# qo-100-generic-filter.net
KiCad netlist of a schematic drawn in EAGLE
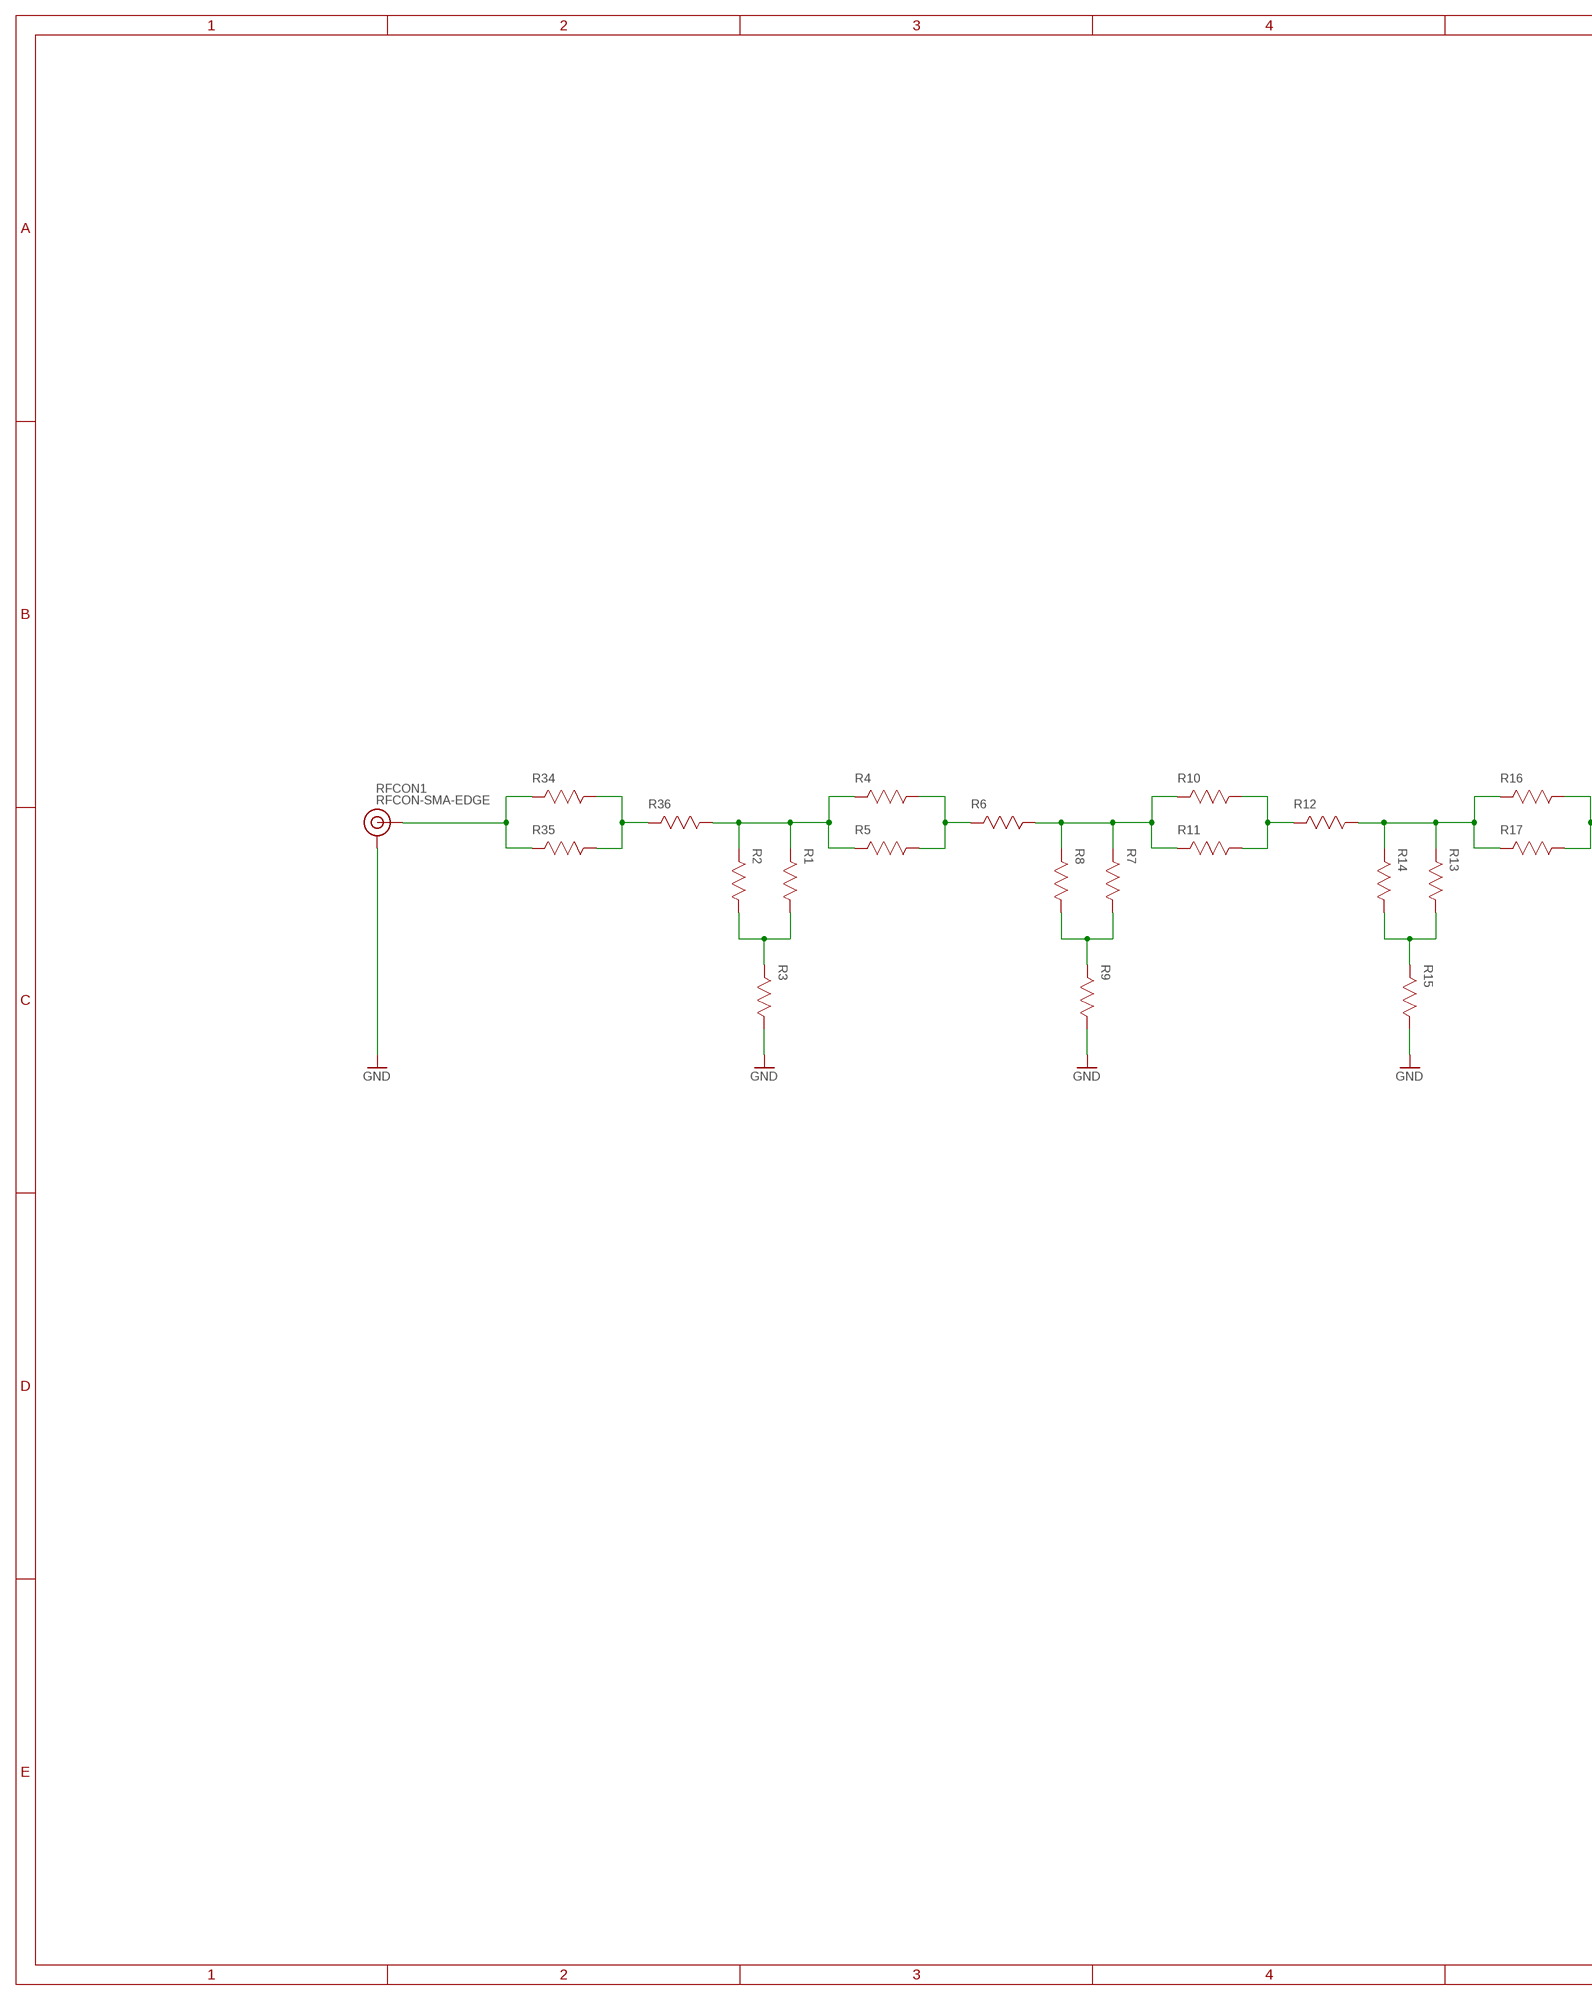
[diagram p0: schematic, sheet 1, part 1 of 2]
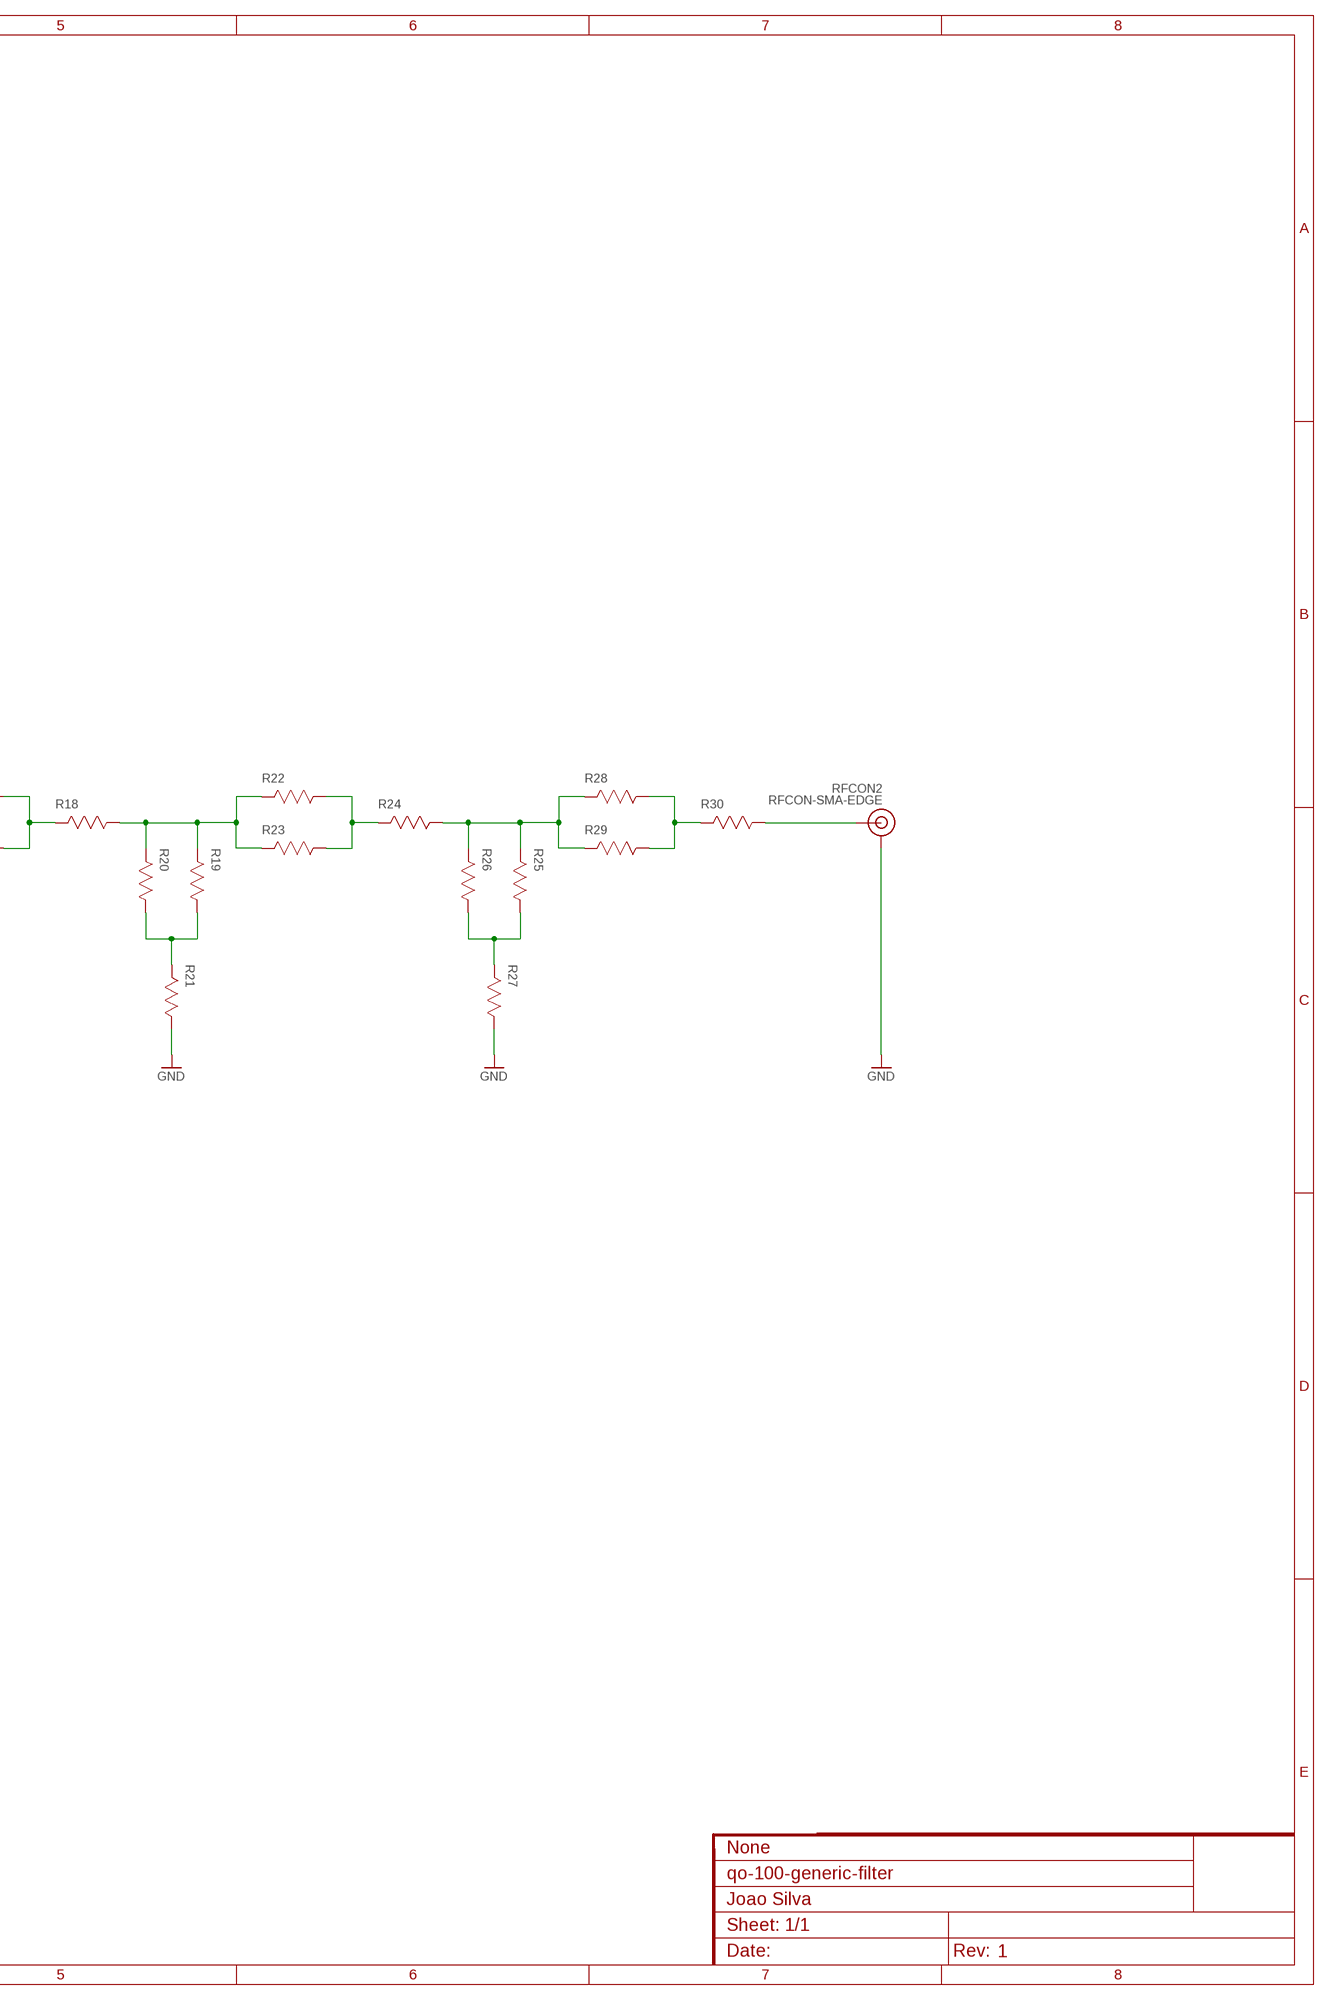
[diagram p1: schematic, sheet 1, part 2 of 2]

(export (version "E")
  (design (tool "Eeschema 10.0.6"))
  (components
    (comp (ref "R1")
      (value "RESISTOR-0603")
      (footprint "eagle-import:RES0603")
      (libsource (lib "eagle-import") (part "RESISTOR-0603"))
    )
    (comp (ref "R2")
      (value "RESISTOR-0603")
      (footprint "eagle-import:RES0603")
      (libsource (lib "eagle-import") (part "RESISTOR-0603"))
    )
    (comp (ref "R3")
      (value "RESISTOR-0603")
      (footprint "eagle-import:RES0603")
      (libsource (lib "eagle-import") (part "RESISTOR-0603"))
    )
    (comp (ref "R4")
      (value "RESISTOR-0603")
      (footprint "eagle-import:RES0603")
      (libsource (lib "eagle-import") (part "RESISTOR-0603"))
    )
    (comp (ref "R5")
      (value "RESISTOR-0603")
      (footprint "eagle-import:RES0603")
      (libsource (lib "eagle-import") (part "RESISTOR-0603"))
    )
    (comp (ref "R6")
      (value "RESISTOR-0603")
      (footprint "eagle-import:RES0603")
      (libsource (lib "eagle-import") (part "RESISTOR-0603"))
    )
    (comp (ref "R7")
      (value "RESISTOR-0603")
      (footprint "eagle-import:RES0603")
      (libsource (lib "eagle-import") (part "RESISTOR-0603"))
    )
    (comp (ref "R8")
      (value "RESISTOR-0603")
      (footprint "eagle-import:RES0603")
      (libsource (lib "eagle-import") (part "RESISTOR-0603"))
    )
    (comp (ref "R9")
      (value "RESISTOR-0603")
      (footprint "eagle-import:RES0603")
      (libsource (lib "eagle-import") (part "RESISTOR-0603"))
    )
    (comp (ref "R10")
      (value "RESISTOR-0603")
      (footprint "eagle-import:RES0603")
      (libsource (lib "eagle-import") (part "RESISTOR-0603"))
    )
    (comp (ref "R11")
      (value "RESISTOR-0603")
      (footprint "eagle-import:RES0603")
      (libsource (lib "eagle-import") (part "RESISTOR-0603"))
    )
    (comp (ref "R12")
      (value "RESISTOR-0603")
      (footprint "eagle-import:RES0603")
      (libsource (lib "eagle-import") (part "RESISTOR-0603"))
    )
    (comp (ref "R13")
      (value "RESISTOR-0603")
      (footprint "eagle-import:RES0603")
      (libsource (lib "eagle-import") (part "RESISTOR-0603"))
    )
    (comp (ref "R14")
      (value "RESISTOR-0603")
      (footprint "eagle-import:RES0603")
      (libsource (lib "eagle-import") (part "RESISTOR-0603"))
    )
    (comp (ref "R15")
      (value "RESISTOR-0603")
      (footprint "eagle-import:RES0603")
      (libsource (lib "eagle-import") (part "RESISTOR-0603"))
    )
    (comp (ref "R16")
      (value "RESISTOR-0603")
      (footprint "eagle-import:RES0603")
      (libsource (lib "eagle-import") (part "RESISTOR-0603"))
    )
    (comp (ref "R17")
      (value "RESISTOR-0603")
      (footprint "eagle-import:RES0603")
      (libsource (lib "eagle-import") (part "RESISTOR-0603"))
    )
    (comp (ref "R18")
      (value "RESISTOR-0603")
      (footprint "eagle-import:RES0603")
      (libsource (lib "eagle-import") (part "RESISTOR-0603"))
    )
    (comp (ref "R19")
      (value "RESISTOR-0603")
      (footprint "eagle-import:RES0603")
      (libsource (lib "eagle-import") (part "RESISTOR-0603"))
    )
    (comp (ref "R20")
      (value "RESISTOR-0603")
      (footprint "eagle-import:RES0603")
      (libsource (lib "eagle-import") (part "RESISTOR-0603"))
    )
    (comp (ref "R21")
      (value "RESISTOR-0603")
      (footprint "eagle-import:RES0603")
      (libsource (lib "eagle-import") (part "RESISTOR-0603"))
    )
    (comp (ref "R22")
      (value "RESISTOR-0603")
      (footprint "eagle-import:RES0603")
      (libsource (lib "eagle-import") (part "RESISTOR-0603"))
    )
    (comp (ref "R23")
      (value "RESISTOR-0603")
      (footprint "eagle-import:RES0603")
      (libsource (lib "eagle-import") (part "RESISTOR-0603"))
    )
    (comp (ref "R24")
      (value "RESISTOR-0603")
      (footprint "eagle-import:RES0603")
      (libsource (lib "eagle-import") (part "RESISTOR-0603"))
    )
    (comp (ref "R25")
      (value "RESISTOR-0603")
      (footprint "eagle-import:RES0603")
      (libsource (lib "eagle-import") (part "RESISTOR-0603"))
    )
    (comp (ref "R26")
      (value "RESISTOR-0603")
      (footprint "eagle-import:RES0603")
      (libsource (lib "eagle-import") (part "RESISTOR-0603"))
    )
    (comp (ref "R27")
      (value "RESISTOR-0603")
      (footprint "eagle-import:RES0603")
      (libsource (lib "eagle-import") (part "RESISTOR-0603"))
    )
    (comp (ref "R28")
      (value "RESISTOR-0603")
      (footprint "eagle-import:RES0603")
      (libsource (lib "eagle-import") (part "RESISTOR-0603"))
    )
    (comp (ref "R29")
      (value "RESISTOR-0603")
      (footprint "eagle-import:RES0603")
      (libsource (lib "eagle-import") (part "RESISTOR-0603"))
    )
    (comp (ref "R30")
      (value "RESISTOR-0603")
      (footprint "eagle-import:RES0603")
      (libsource (lib "eagle-import") (part "RESISTOR-0603"))
    )
    (comp (ref "R34")
      (value "RESISTOR-0603")
      (footprint "eagle-import:RES0603")
      (libsource (lib "eagle-import") (part "RESISTOR-0603"))
    )
    (comp (ref "R35")
      (value "RESISTOR-0603")
      (footprint "eagle-import:RES0603")
      (libsource (lib "eagle-import") (part "RESISTOR-0603"))
    )
    (comp (ref "R36")
      (value "RESISTOR-0603")
      (footprint "eagle-import:RES0603")
      (libsource (lib "eagle-import") (part "RESISTOR-0603"))
    )
    (comp (ref "RFCON1")
      (value "RFCON-SMA-EDGE")
      (footprint "eagle-import:SMA-EDGE")
      (libsource (lib "eagle-import") (part "RFCON-SMA-EDGE"))
    )
    (comp (ref "RFCON2")
      (value "RFCON-SMA-EDGE")
      (footprint "eagle-import:SMA-EDGE")
      (libsource (lib "eagle-import") (part "RFCON-SMA-EDGE"))
    )
  )
  (nets
    (net (code "1") (name "GND") (class "Default")
      (node (ref "R15") (pin "1") (pinfunction "1_1") (pintype "passive"))
      (node (ref "R21") (pin "1") (pinfunction "1_1") (pintype "passive"))
      (node (ref "R27") (pin "1") (pinfunction "1_1") (pintype "passive"))
      (node (ref "R3") (pin "1") (pinfunction "1_1") (pintype "passive"))
      (node (ref "R9") (pin "1") (pinfunction "1_1") (pintype "passive"))
      (node (ref "RFCON1") (pin "GND@0") (pinfunction "GND_GND@0") (pintype "bidirectional"))
      (node (ref "RFCON1") (pin "GND@1") (pinfunction "GND_GND@1") (pintype "bidirectional"))
      (node (ref "RFCON1") (pin "GND@2") (pinfunction "GND_GND@2") (pintype "bidirectional"))
      (node (ref "RFCON1") (pin "GND@3") (pinfunction "GND_GND@3") (pintype "bidirectional"))
      (node (ref "RFCON2") (pin "GND@0") (pinfunction "GND_GND@0") (pintype "bidirectional"))
      (node (ref "RFCON2") (pin "GND@1") (pinfunction "GND_GND@1") (pintype "bidirectional"))
      (node (ref "RFCON2") (pin "GND@2") (pinfunction "GND_GND@2") (pintype "bidirectional"))
      (node (ref "RFCON2") (pin "GND@3") (pinfunction "GND_GND@3") (pintype "bidirectional"))
    )
    (net (code "2") (name "Net-(R1-Pad1)") (class "Default")
      (node (ref "R1") (pin "1") (pinfunction "1_1") (pintype "passive"))
      (node (ref "R2") (pin "1") (pinfunction "1_1") (pintype "passive"))
      (node (ref "R3") (pin "2") (pinfunction "2_2") (pintype "passive"))
    )
    (net (code "3") (name "Net-(R1-Pad2)") (class "Default")
      (node (ref "R1") (pin "2") (pinfunction "2_2") (pintype "passive"))
      (node (ref "R2") (pin "2") (pinfunction "2_2") (pintype "passive"))
      (node (ref "R36") (pin "1") (pinfunction "1_1") (pintype "passive"))
      (node (ref "R4") (pin "2") (pinfunction "2_2") (pintype "passive"))
      (node (ref "R5") (pin "2") (pinfunction "2_2") (pintype "passive"))
    )
    (net (code "4") (name "Net-(R4-Pad1)") (class "Default")
      (node (ref "R4") (pin "1") (pinfunction "1_1") (pintype "passive"))
      (node (ref "R5") (pin "1") (pinfunction "1_1") (pintype "passive"))
      (node (ref "R6") (pin "2") (pinfunction "2_2") (pintype "passive"))
    )
    (net (code "5") (name "Net-(R7-Pad1)") (class "Default")
      (node (ref "R7") (pin "1") (pinfunction "1_1") (pintype "passive"))
      (node (ref "R8") (pin "1") (pinfunction "1_1") (pintype "passive"))
      (node (ref "R9") (pin "2") (pinfunction "2_2") (pintype "passive"))
    )
    (net (code "6") (name "Net-(R10-Pad1)") (class "Default")
      (node (ref "R10") (pin "1") (pinfunction "1_1") (pintype "passive"))
      (node (ref "R11") (pin "1") (pinfunction "1_1") (pintype "passive"))
      (node (ref "R12") (pin "2") (pinfunction "2_2") (pintype "passive"))
    )
    (net (code "7") (name "Net-(R10-Pad2)") (class "Default")
      (node (ref "R10") (pin "2") (pinfunction "2_2") (pintype "passive"))
      (node (ref "R11") (pin "2") (pinfunction "2_2") (pintype "passive"))
      (node (ref "R6") (pin "1") (pinfunction "1_1") (pintype "passive"))
      (node (ref "R7") (pin "2") (pinfunction "2_2") (pintype "passive"))
      (node (ref "R8") (pin "2") (pinfunction "2_2") (pintype "passive"))
    )
    (net (code "8") (name "Net-(R12-Pad1)") (class "Default")
      (node (ref "R12") (pin "1") (pinfunction "1_1") (pintype "passive"))
      (node (ref "R13") (pin "2") (pinfunction "2_2") (pintype "passive"))
      (node (ref "R14") (pin "2") (pinfunction "2_2") (pintype "passive"))
      (node (ref "R16") (pin "2") (pinfunction "2_2") (pintype "passive"))
      (node (ref "R17") (pin "2") (pinfunction "2_2") (pintype "passive"))
    )
    (net (code "9") (name "Net-(R13-Pad1)") (class "Default")
      (node (ref "R13") (pin "1") (pinfunction "1_1") (pintype "passive"))
      (node (ref "R14") (pin "1") (pinfunction "1_1") (pintype "passive"))
      (node (ref "R15") (pin "2") (pinfunction "2_2") (pintype "passive"))
    )
    (net (code "10") (name "Net-(R16-Pad1)") (class "Default")
      (node (ref "R16") (pin "1") (pinfunction "1_1") (pintype "passive"))
      (node (ref "R17") (pin "1") (pinfunction "1_1") (pintype "passive"))
      (node (ref "R18") (pin "2") (pinfunction "2_2") (pintype "passive"))
    )
    (net (code "11") (name "Net-(R18-Pad1)") (class "Default")
      (node (ref "R18") (pin "1") (pinfunction "1_1") (pintype "passive"))
      (node (ref "R19") (pin "2") (pinfunction "2_2") (pintype "passive"))
      (node (ref "R20") (pin "2") (pinfunction "2_2") (pintype "passive"))
      (node (ref "R22") (pin "2") (pinfunction "2_2") (pintype "passive"))
      (node (ref "R23") (pin "2") (pinfunction "2_2") (pintype "passive"))
    )
    (net (code "12") (name "Net-(R19-Pad1)") (class "Default")
      (node (ref "R19") (pin "1") (pinfunction "1_1") (pintype "passive"))
      (node (ref "R20") (pin "1") (pinfunction "1_1") (pintype "passive"))
      (node (ref "R21") (pin "2") (pinfunction "2_2") (pintype "passive"))
    )
    (net (code "13") (name "Net-(R22-Pad1)") (class "Default")
      (node (ref "R22") (pin "1") (pinfunction "1_1") (pintype "passive"))
      (node (ref "R23") (pin "1") (pinfunction "1_1") (pintype "passive"))
      (node (ref "R24") (pin "2") (pinfunction "2_2") (pintype "passive"))
    )
    (net (code "14") (name "Net-(R24-Pad1)") (class "Default")
      (node (ref "R24") (pin "1") (pinfunction "1_1") (pintype "passive"))
      (node (ref "R25") (pin "2") (pinfunction "2_2") (pintype "passive"))
      (node (ref "R26") (pin "2") (pinfunction "2_2") (pintype "passive"))
      (node (ref "R28") (pin "2") (pinfunction "2_2") (pintype "passive"))
      (node (ref "R29") (pin "2") (pinfunction "2_2") (pintype "passive"))
    )
    (net (code "15") (name "Net-(R25-Pad1)") (class "Default")
      (node (ref "R25") (pin "1") (pinfunction "1_1") (pintype "passive"))
      (node (ref "R26") (pin "1") (pinfunction "1_1") (pintype "passive"))
      (node (ref "R27") (pin "2") (pinfunction "2_2") (pintype "passive"))
    )
    (net (code "16") (name "Net-(R28-Pad1)") (class "Default")
      (node (ref "R28") (pin "1") (pinfunction "1_1") (pintype "passive"))
      (node (ref "R29") (pin "1") (pinfunction "1_1") (pintype "passive"))
      (node (ref "R30") (pin "2") (pinfunction "2_2") (pintype "passive"))
    )
    (net (code "17") (name "Net-(R34-Pad1)") (class "Default")
      (node (ref "R34") (pin "1") (pinfunction "1_1") (pintype "passive"))
      (node (ref "R35") (pin "1") (pinfunction "1_1") (pintype "passive"))
      (node (ref "R36") (pin "2") (pinfunction "2_2") (pintype "passive"))
    )
    (net (code "18") (name "Net-(RFCON1-SIGNAL)") (class "Default")
      (node (ref "R34") (pin "2") (pinfunction "2_2") (pintype "passive"))
      (node (ref "R35") (pin "2") (pinfunction "2_2") (pintype "passive"))
      (node (ref "RFCON1") (pin "SIG") (pinfunction "SIGNAL_SIG") (pintype "bidirectional"))
    )
    (net (code "19") (name "Net-(RFCON2-SIGNAL)") (class "Default")
      (node (ref "R30") (pin "1") (pinfunction "1_1") (pintype "passive"))
      (node (ref "RFCON2") (pin "SIG") (pinfunction "SIGNAL_SIG") (pintype "bidirectional"))
    )
  )
)
